# eii-psu-psb.net
KiCad netlist of a schematic drawn in EAGLE
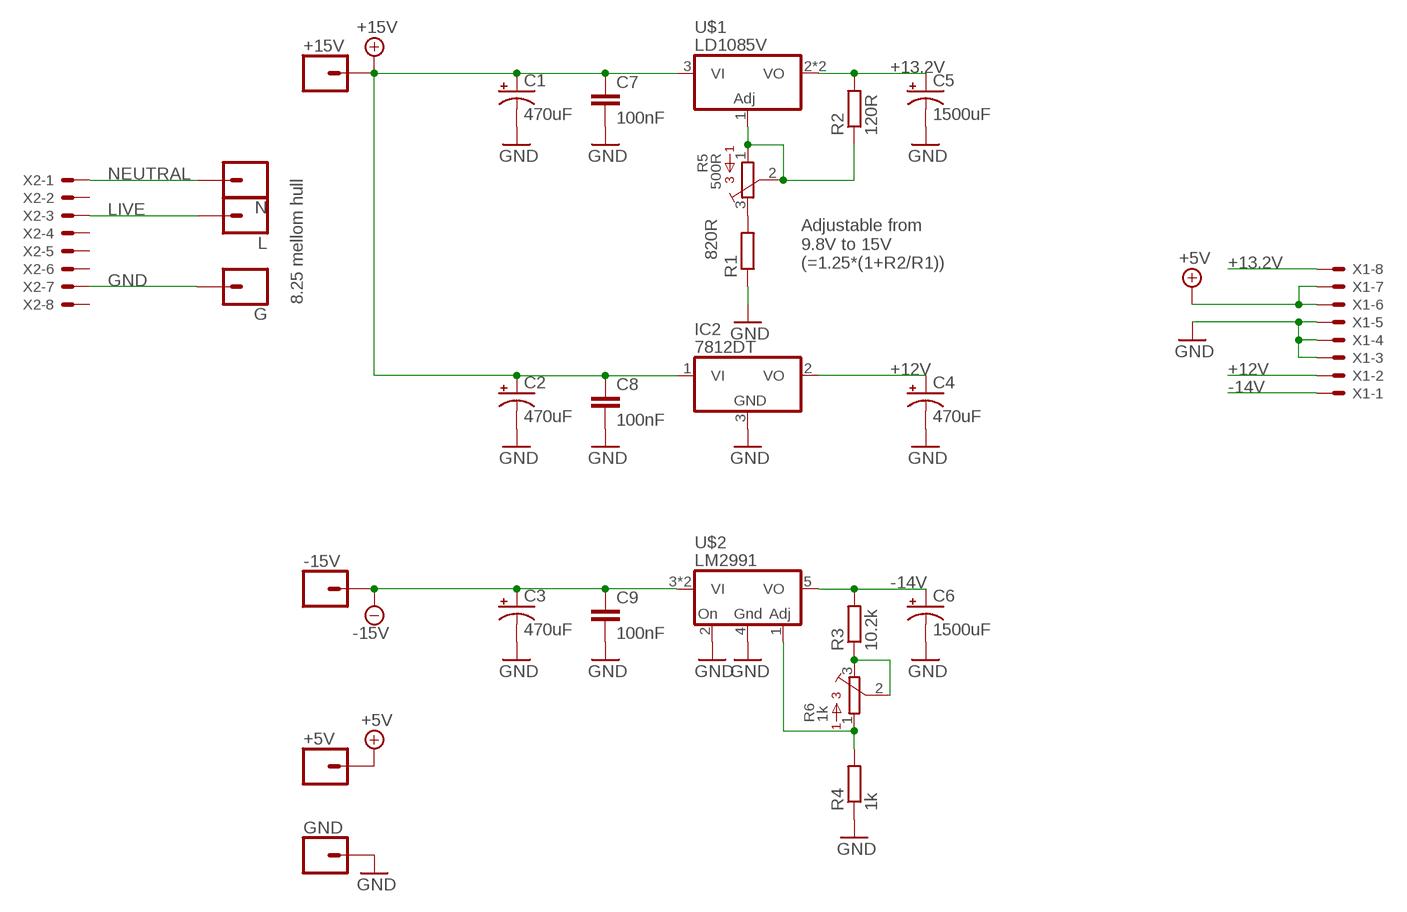
[diagram p0: schematic, sheet 1]

(export (version "E")
  (design (tool "Eeschema 10.0.6"))
  (components
    (comp (ref "+5V")
      (value "CONN_01PTH_2MM")
      (footprint "eagle-import:1X01_2MM")
      (libsource (lib "eagle-import") (part "CONN_01PTH_2MM"))
    )
    (comp (ref "+15V")
      (value "CONN_01PTH_2MM")
      (footprint "eagle-import:1X01_2MM")
      (libsource (lib "eagle-import") (part "CONN_01PTH_2MM"))
    )
    (comp (ref "-15V")
      (value "CONN_01PTH_2MM")
      (footprint "eagle-import:1X01_2MM")
      (libsource (lib "eagle-import") (part "CONN_01PTH_2MM"))
    )
    (comp (ref "C1")
      (value "470uF")
      (footprint "eagle-import:E5-10,5")
      (libsource (lib "eagle-import") (part "CPOL-USE5-10.5"))
    )
    (comp (ref "C2")
      (value "470uF")
      (footprint "eagle-import:E5-10,5")
      (libsource (lib "eagle-import") (part "CPOL-USE5-10.5"))
    )
    (comp (ref "C3")
      (value "470uF")
      (footprint "eagle-import:E5-10,5")
      (libsource (lib "eagle-import") (part "CPOL-USE5-10.5"))
    )
    (comp (ref "C4")
      (value "470uF")
      (footprint "eagle-import:E5-10,5")
      (libsource (lib "eagle-import") (part "CPOL-USE5-10.5"))
    )
    (comp (ref "C5")
      (value "1500uF")
      (footprint "eagle-import:E5-13")
      (libsource (lib "eagle-import") (part "CPOL-USE5-13"))
    )
    (comp (ref "C6")
      (value "1500uF")
      (footprint "eagle-import:E5-13")
      (libsource (lib "eagle-import") (part "CPOL-USE5-13"))
    )
    (comp (ref "C7")
      (value "100nF")
      (footprint "eagle-import:C050-030X075")
      (libsource (lib "eagle-import") (part "C-EU050-030X075"))
    )
    (comp (ref "C8")
      (value "100nF")
      (footprint "eagle-import:C050-030X075")
      (libsource (lib "eagle-import") (part "C-EU050-030X075"))
    )
    (comp (ref "C9")
      (value "100nF")
      (footprint "eagle-import:C050-030X075")
      (libsource (lib "eagle-import") (part "C-EU050-030X075"))
    )
    (comp (ref "G")
      (value "CONN_01PTH_2MM")
      (footprint "eagle-import:1X01_2MM")
      (libsource (lib "eagle-import") (part "CONN_01PTH_2MM"))
    )
    (comp (ref "GND")
      (value "CONN_01PTH_2MM")
      (footprint "eagle-import:1X01_2MM")
      (libsource (lib "eagle-import") (part "CONN_01PTH_2MM"))
    )
    (comp (ref "IC2")
      (value "7812DT")
      (footprint "eagle-import:TO252")
      (libsource (lib "eagle-import") (part "78DT12"))
    )
    (comp (ref "L")
      (value "CONN_01PTH_2MM")
      (footprint "eagle-import:1X01_2MM")
      (libsource (lib "eagle-import") (part "CONN_01PTH_2MM"))
    )
    (comp (ref "N")
      (value "CONN_01PTH_2MM")
      (footprint "eagle-import:1X01_2MM")
      (libsource (lib "eagle-import") (part "CONN_01PTH_2MM"))
    )
    (comp (ref "R1")
      (value "820R")
      (footprint "eagle-import:R1206")
      (libsource (lib "eagle-import") (part "R-EU_R1206"))
    )
    (comp (ref "R2")
      (value "120R")
      (footprint "eagle-import:R1206")
      (libsource (lib "eagle-import") (part "R-EU_R1206"))
    )
    (comp (ref "R3")
      (value "10.2k")
      (footprint "eagle-import:R1206")
      (libsource (lib "eagle-import") (part "R-EU_R1206"))
    )
    (comp (ref "R4")
      (value "1k")
      (footprint "eagle-import:R1206")
      (libsource (lib "eagle-import") (part "R-EU_R1206"))
    )
    (comp (ref "R5")
      (value "500R")
      (footprint "eagle-import:3362P")
      (libsource (lib "eagle-import") (part "3362P"))
    )
    (comp (ref "R6")
      (value "1k")
      (footprint "eagle-import:3362P")
      (libsource (lib "eagle-import") (part "3362P"))
    )
    (comp (ref "U$1")
      (value "LD1085V")
      (footprint "eagle-import:TO263-3J")
      (libsource (lib "eagle-import") (part "LD1085V"))
    )
    (comp (ref "U$2")
      (value "LM2991")
      (footprint "eagle-import:TO263-5J")
      (libsource (lib "eagle-import") (part "LM2991"))
    )
    (comp (ref "X1")
      (value "KK-156-8")
      (footprint "eagle-import:KK-156-8")
      (fields (field (name "MF") "MOLEX"))
      (libsource (lib "eagle-import") (part "KK-156-8"))
    )
    (comp (ref "X2")
      (value "KK-156-8")
      (footprint "eagle-import:KK-156-8")
      (fields (field (name "MF") "MOLEX"))
      (libsource (lib "eagle-import") (part "KK-156-8"))
    )
  )
  (nets
    (net (code "1") (name "+5V") (class "Default")
      (node (ref "+5V") (pin "1") (pinfunction "1_1") (pintype "passive"))
      (node (ref "X1") (pin "6") (pinfunction "S_6") (pintype "passive"))
      (node (ref "X1") (pin "7") (pinfunction "S_7") (pintype "passive"))
    )
    (net (code "2") (name "+15V") (class "Default")
      (node (ref "+15V") (pin "1") (pinfunction "1_1") (pintype "passive"))
      (node (ref "C1") (pin "+") (pinfunction "+_+") (pintype "passive"))
      (node (ref "C2") (pin "+") (pinfunction "+_+") (pintype "passive"))
      (node (ref "C7") (pin "1") (pinfunction "1_1") (pintype "passive"))
      (node (ref "C8") (pin "1") (pinfunction "1_1") (pintype "passive"))
      (node (ref "IC2") (pin "1") (pinfunction "VI_1") (pintype "input"))
      (node (ref "U$1") (pin "3") (pinfunction "VI_3") (pintype "input"))
    )
    (net (code "3") (name "-15V") (class "Default")
      (node (ref "-15V") (pin "1") (pinfunction "1_1") (pintype "passive"))
      (node (ref "C3") (pin "+") (pinfunction "+_+") (pintype "passive"))
      (node (ref "C9") (pin "1") (pinfunction "1_1") (pintype "passive"))
      (node (ref "U$2") (pin "3") (pinfunction "VI_3") (pintype "input"))
      (node (ref "U$2") (pin "6") (pinfunction "VI_6") (pintype "input"))
    )
    (net (code "4") (name "/+12V") (class "Default")
      (node (ref "C4") (pin "+") (pinfunction "+_+") (pintype "passive"))
      (node (ref "IC2") (pin "2") (pinfunction "VO_2") (pintype "passive"))
      (node (ref "X1") (pin "2") (pinfunction "S_2") (pintype "passive"))
    )
    (net (code "5") (name "/+13.2V") (class "Default")
      (node (ref "C5") (pin "+") (pinfunction "+_+") (pintype "passive"))
      (node (ref "R2") (pin "2") (pinfunction "2_2") (pintype "passive"))
      (node (ref "U$1") (pin "2") (pinfunction "VO_2") (pintype "passive"))
      (node (ref "U$1") (pin "TAB") (pinfunction "VO_TAB") (pintype "passive"))
      (node (ref "X1") (pin "8") (pinfunction "S_8") (pintype "passive"))
    )
    (net (code "6") (name "/-14V") (class "Default")
      (node (ref "C6") (pin "+") (pinfunction "+_+") (pintype "passive"))
      (node (ref "R3") (pin "2") (pinfunction "2_2") (pintype "passive"))
      (node (ref "U$2") (pin "5") (pinfunction "VO_5") (pintype "passive"))
      (node (ref "X1") (pin "1") (pinfunction "S_1") (pintype "passive"))
    )
    (net (code "7") (name "/LIVE") (class "Default")
      (node (ref "L") (pin "1") (pinfunction "1_1") (pintype "passive"))
      (node (ref "X2") (pin "3") (pinfunction "S_3") (pintype "passive"))
    )
    (net (code "8") (name "/NEUTRAL") (class "Default")
      (node (ref "N") (pin "1") (pinfunction "1_1") (pintype "passive"))
      (node (ref "X2") (pin "1") (pinfunction "S_1") (pintype "passive"))
    )
    (net (code "9") (name "GND") (class "Default")
      (node (ref "C1") (pin "-") (pinfunction "-_-") (pintype "passive"))
      (node (ref "C2") (pin "-") (pinfunction "-_-") (pintype "passive"))
      (node (ref "C3") (pin "-") (pinfunction "-_-") (pintype "passive"))
      (node (ref "C4") (pin "-") (pinfunction "-_-") (pintype "passive"))
      (node (ref "C5") (pin "-") (pinfunction "-_-") (pintype "passive"))
      (node (ref "C6") (pin "-") (pinfunction "-_-") (pintype "passive"))
      (node (ref "C7") (pin "2") (pinfunction "2_2") (pintype "passive"))
      (node (ref "C8") (pin "2") (pinfunction "2_2") (pintype "passive"))
      (node (ref "C9") (pin "2") (pinfunction "2_2") (pintype "passive"))
      (node (ref "G") (pin "1") (pinfunction "1_1") (pintype "passive"))
      (node (ref "GND") (pin "1") (pinfunction "1_1") (pintype "passive"))
      (node (ref "IC2") (pin "3") (pinfunction "GND_3") (pintype "passive"))
      (node (ref "R1") (pin "1") (pinfunction "1_1") (pintype "passive"))
      (node (ref "R4") (pin "1") (pinfunction "1_1") (pintype "passive"))
      (node (ref "U$2") (pin "2") (pinfunction "ON_2") (pintype "passive"))
      (node (ref "U$2") (pin "4") (pinfunction "GND_4") (pintype "passive"))
      (node (ref "X1") (pin "3") (pinfunction "S_3") (pintype "passive"))
      (node (ref "X1") (pin "4") (pinfunction "S_4") (pintype "passive"))
      (node (ref "X1") (pin "5") (pinfunction "S_5") (pintype "passive"))
      (node (ref "X2") (pin "7") (pinfunction "S_7") (pintype "passive"))
    )
    (net (code "10") (name "Net-(R1-Pad2)") (class "Default")
      (node (ref "R1") (pin "2") (pinfunction "2_2") (pintype "passive"))
      (node (ref "R5") (pin "3") (pinfunction "3_3") (pintype "passive"))
    )
    (net (code "11") (name "Net-(R3-Pad1)") (class "Default")
      (node (ref "R3") (pin "1") (pinfunction "1_1") (pintype "passive"))
      (node (ref "R6") (pin "2") (pinfunction "2_2") (pintype "passive"))
      (node (ref "R6") (pin "3") (pinfunction "3_3") (pintype "passive"))
    )
    (net (code "12") (name "Net-(U$1-ADJ)") (class "Default")
      (node (ref "R2") (pin "1") (pinfunction "1_1") (pintype "passive"))
      (node (ref "R5") (pin "1") (pinfunction "1_1") (pintype "passive"))
      (node (ref "R5") (pin "2") (pinfunction "2_2") (pintype "passive"))
      (node (ref "U$1") (pin "1") (pinfunction "ADJ_1") (pintype "passive"))
    )
    (net (code "13") (name "Net-(U$2-ADJ)") (class "Default")
      (node (ref "R4") (pin "2") (pinfunction "2_2") (pintype "passive"))
      (node (ref "R6") (pin "1") (pinfunction "1_1") (pintype "passive"))
      (node (ref "U$2") (pin "1") (pinfunction "ADJ_1") (pintype "passive"))
    )
    (net (code "14") (name "unconnected-(X2B-S-Pad2)") (class "Default")
      (node (ref "X2") (pin "2") (pinfunction "S_2") (pintype "passive"))
    )
    (net (code "15") (name "unconnected-(X2D-S-Pad4)") (class "Default")
      (node (ref "X2") (pin "4") (pinfunction "S_4") (pintype "passive"))
    )
    (net (code "16") (name "unconnected-(X2E-S-Pad5)") (class "Default")
      (node (ref "X2") (pin "5") (pinfunction "S_5") (pintype "passive"))
    )
    (net (code "17") (name "unconnected-(X2F-S-Pad6)") (class "Default")
      (node (ref "X2") (pin "6") (pinfunction "S_6") (pintype "passive"))
    )
    (net (code "18") (name "unconnected-(X2H-S-Pad8)") (class "Default")
      (node (ref "X2") (pin "8") (pinfunction "S_8") (pintype "passive"))
    )
  )
)
